# Skaarhoj_BI8-SE-C30.net
KiCad netlist of a schematic drawn in EAGLE
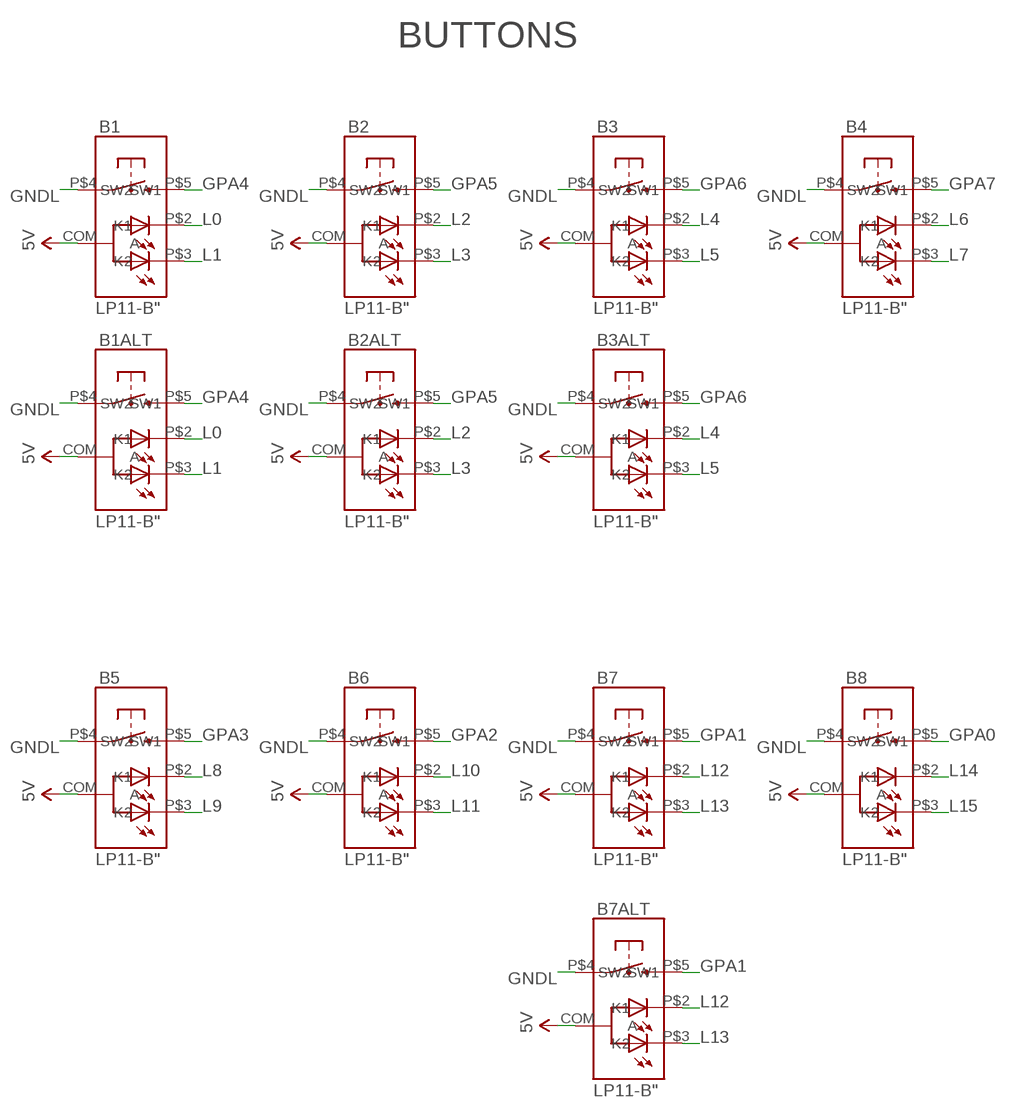
[diagram p0: schematic, sheet 1, part 1 of 2]
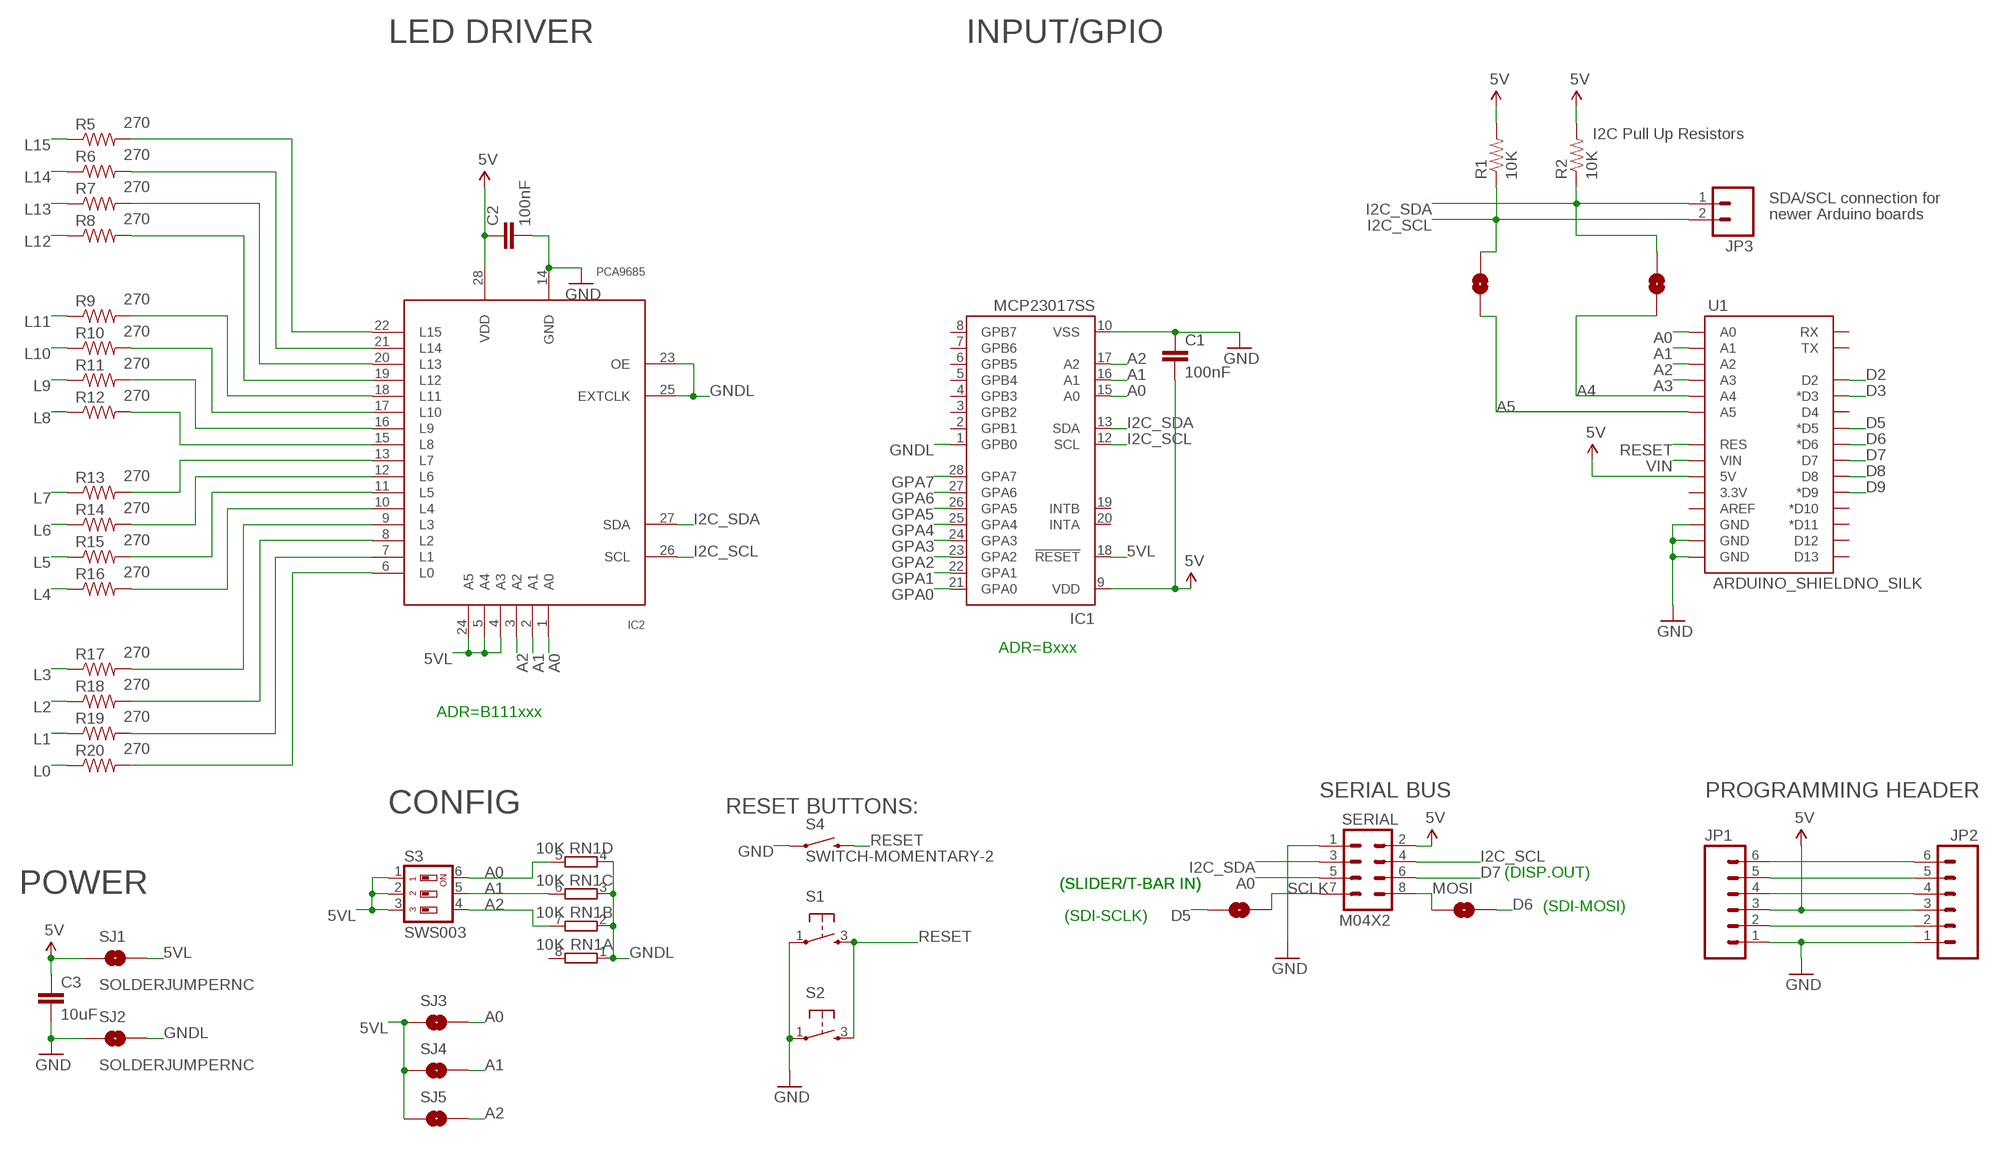
[diagram p1: schematic, sheet 1, part 2 of 2]

(export (version "E")
  (design (tool "Eeschema 10.0.6"))
  (components
    (comp (ref "B1")
      (value "LP11-B\"")
      (footprint "eagle-import:LP11")
      (libsource (lib "eagle-import") (part "LP11-B{dblquote}"))
    )
    (comp (ref "B1ALT")
      (value "LP11-B\"")
      (footprint "eagle-import:LP11")
      (libsource (lib "eagle-import") (part "LP11-B{dblquote}"))
    )
    (comp (ref "B2")
      (value "LP11-B\"")
      (footprint "eagle-import:LP11")
      (libsource (lib "eagle-import") (part "LP11-B{dblquote}"))
    )
    (comp (ref "B2ALT")
      (value "LP11-B\"")
      (footprint "eagle-import:LP11")
      (libsource (lib "eagle-import") (part "LP11-B{dblquote}"))
    )
    (comp (ref "B3")
      (value "LP11-B\"")
      (footprint "eagle-import:LP11")
      (libsource (lib "eagle-import") (part "LP11-B{dblquote}"))
    )
    (comp (ref "B3ALT")
      (value "LP11-B\"")
      (footprint "eagle-import:LP11")
      (libsource (lib "eagle-import") (part "LP11-B{dblquote}"))
    )
    (comp (ref "B4")
      (value "LP11-B\"")
      (footprint "eagle-import:LP11")
      (libsource (lib "eagle-import") (part "LP11-B{dblquote}"))
    )
    (comp (ref "B5")
      (value "LP11-B\"")
      (footprint "eagle-import:LP11")
      (libsource (lib "eagle-import") (part "LP11-B{dblquote}"))
    )
    (comp (ref "B6")
      (value "LP11-B\"")
      (footprint "eagle-import:LP11")
      (libsource (lib "eagle-import") (part "LP11-B{dblquote}"))
    )
    (comp (ref "B7")
      (value "LP11-B\"")
      (footprint "eagle-import:LP11")
      (libsource (lib "eagle-import") (part "LP11-B{dblquote}"))
    )
    (comp (ref "B7ALT")
      (value "LP11-B\"")
      (footprint "eagle-import:LP11")
      (libsource (lib "eagle-import") (part "LP11-B{dblquote}"))
    )
    (comp (ref "B8")
      (value "LP11-B\"")
      (footprint "eagle-import:LP11")
      (libsource (lib "eagle-import") (part "LP11-B{dblquote}"))
    )
    (comp (ref "C1")
      (value "100nF")
      (footprint "eagle-import:0603-CAP")
      (libsource (lib "eagle-import") (part "CAP0603-CAP"))
    )
    (comp (ref "C2")
      (value "100nF")
      (footprint "eagle-import:0603-CAP")
      (libsource (lib "eagle-import") (part "CAP0603-CAP"))
    )
    (comp (ref "C3")
      (value "10uF")
      (footprint "eagle-import:0805")
      (libsource (lib "eagle-import") (part "CAP0805"))
    )
    (comp (ref "IC1")
      (value "MCP23017SS")
      (footprint "eagle-import:SSOP28")
      (fields
        (field (name "MF") "MICROCHIP")
        (field (name "MPN") "MCP23017-E/SS")
        (field (name "MPN_1") "MCP23017-E/SS")
        (field (name "OC_FARNELL") "1467674")
        (field (name "OC_NEWARK") "31K2960")
      )
      (libsource (lib "eagle-import") (part "MCP23017SS"))
    )
    (comp (ref "IC2")
      (value "PCA9685")
      (footprint "eagle-import:TSSOP28")
      (libsource (lib "eagle-import") (part "PCA9685"))
    )
    (comp (ref "JP1")
      (value "M06POLAR")
      (footprint "eagle-import:MOLEX-1X6")
      (libsource (lib "eagle-import") (part "M06POLAR"))
    )
    (comp (ref "JP2")
      (value "M06POLAR")
      (footprint "eagle-import:MOLEX-1X6")
      (libsource (lib "eagle-import") (part "M06POLAR"))
    )
    (comp (ref "JP3")
      (value "M02PTH")
      (footprint "eagle-import:1X02")
      (libsource (lib "eagle-import") (part "M02PTH"))
    )
    (comp (ref "MOSI->D6")
      (value "SOLDERJUMPERNC")
      (footprint "eagle-import:SJ_2S")
      (libsource (lib "eagle-import") (part "SOLDERJUMPERNC"))
    )
    (comp (ref "R1")
      (value "10K")
      (footprint "eagle-import:0603-RES")
      (libsource (lib "eagle-import") (part "RESISTOR0603-RES"))
    )
    (comp (ref "R2")
      (value "10K")
      (footprint "eagle-import:0603-RES")
      (libsource (lib "eagle-import") (part "RESISTOR0603-RES"))
    )
    (comp (ref "R5")
      (value "270")
      (footprint "eagle-import:0603-RES")
      (libsource (lib "eagle-import") (part "RESISTOR0603-RES"))
    )
    (comp (ref "R6")
      (value "270")
      (footprint "eagle-import:0603-RES")
      (libsource (lib "eagle-import") (part "RESISTOR0603-RES"))
    )
    (comp (ref "R7")
      (value "270")
      (footprint "eagle-import:0603-RES")
      (libsource (lib "eagle-import") (part "RESISTOR0603-RES"))
    )
    (comp (ref "R8")
      (value "270")
      (footprint "eagle-import:0603-RES")
      (libsource (lib "eagle-import") (part "RESISTOR0603-RES"))
    )
    (comp (ref "R9")
      (value "270")
      (footprint "eagle-import:0603-RES")
      (libsource (lib "eagle-import") (part "RESISTOR0603-RES"))
    )
    (comp (ref "R10")
      (value "270")
      (footprint "eagle-import:0603-RES")
      (libsource (lib "eagle-import") (part "RESISTOR0603-RES"))
    )
    (comp (ref "R11")
      (value "270")
      (footprint "eagle-import:0603-RES")
      (libsource (lib "eagle-import") (part "RESISTOR0603-RES"))
    )
    (comp (ref "R12")
      (value "270")
      (footprint "eagle-import:0603-RES")
      (libsource (lib "eagle-import") (part "RESISTOR0603-RES"))
    )
    (comp (ref "R13")
      (value "270")
      (footprint "eagle-import:0603-RES")
      (libsource (lib "eagle-import") (part "RESISTOR0603-RES"))
    )
    (comp (ref "R14")
      (value "270")
      (footprint "eagle-import:0603-RES")
      (libsource (lib "eagle-import") (part "RESISTOR0603-RES"))
    )
    (comp (ref "R15")
      (value "270")
      (footprint "eagle-import:0603-RES")
      (libsource (lib "eagle-import") (part "RESISTOR0603-RES"))
    )
    (comp (ref "R16")
      (value "270")
      (footprint "eagle-import:0603-RES")
      (libsource (lib "eagle-import") (part "RESISTOR0603-RES"))
    )
    (comp (ref "R17")
      (value "270")
      (footprint "eagle-import:0603-RES")
      (libsource (lib "eagle-import") (part "RESISTOR0603-RES"))
    )
    (comp (ref "R18")
      (value "270")
      (footprint "eagle-import:0603-RES")
      (libsource (lib "eagle-import") (part "RESISTOR0603-RES"))
    )
    (comp (ref "R19")
      (value "270")
      (footprint "eagle-import:0603-RES")
      (libsource (lib "eagle-import") (part "RESISTOR0603-RES"))
    )
    (comp (ref "R20")
      (value "270")
      (footprint "eagle-import:0603-RES")
      (libsource (lib "eagle-import") (part "RESISTOR0603-RES"))
    )
    (comp (ref "RN1")
      (value "10K")
      (footprint "eagle-import:CAY16_HAND")
      (libsource (lib "eagle-import") (part "4R-NCAY16"))
    )
    (comp (ref "S1")
      (value "TAC_SWITCH")
      (footprint "eagle-import:PUSHBUTTON")
      (libsource (lib "eagle-import") (part "TAC_SWITCH"))
    )
    (comp (ref "S2")
      (value "TAC_SWITCH")
      (footprint "eagle-import:PUSHBUTTON")
      (libsource (lib "eagle-import") (part "TAC_SWITCH"))
    )
    (comp (ref "S3")
      (value "SWS003")
      (footprint "eagle-import:SMS-003")
      (libsource (lib "eagle-import") (part "SWS003"))
    )
    (comp (ref "S3->A2")
      (value "SOLDERJUMPERNC")
      (footprint "eagle-import:SJ_2S")
      (libsource (lib "eagle-import") (part "SOLDERJUMPERNC"))
    )
    (comp (ref "S3->A3")
      (value "SOLDERJUMPERNC")
      (footprint "eagle-import:SJ_2S")
      (libsource (lib "eagle-import") (part "SOLDERJUMPERNC"))
    )
    (comp (ref "S4")
      (value "SWITCH-MOMENTARY-2")
      (footprint "eagle-import:TACTILE_SWITCH_TALL")
      (libsource (lib "eagle-import") (part "SWITCH-MOMENTARY-2"))
    )
    (comp (ref "SCLK->D5")
      (value "SOLDERJUMPERNC")
      (footprint "eagle-import:SJ_2S")
      (libsource (lib "eagle-import") (part "SOLDERJUMPERNC"))
    )
    (comp (ref "SERIAL")
      (value "M04X2")
      (footprint "eagle-import:2X4")
      (libsource (lib "eagle-import") (part "M04X2"))
    )
    (comp (ref "SJ1")
      (value "SOLDERJUMPERNC")
      (footprint "eagle-import:SJ_2S")
      (libsource (lib "eagle-import") (part "SOLDERJUMPERNC"))
    )
    (comp (ref "SJ2")
      (value "SOLDERJUMPERNC")
      (footprint "eagle-import:SJ_2S")
      (libsource (lib "eagle-import") (part "SOLDERJUMPERNC"))
    )
    (comp (ref "SJ3")
      (value "SOLDERJUMPERNC")
      (footprint "eagle-import:SJ_2S")
      (libsource (lib "eagle-import") (part "SOLDERJUMPERNC"))
    )
    (comp (ref "SJ4")
      (value "SOLDERJUMPERNC")
      (footprint "eagle-import:SJ_2S")
      (libsource (lib "eagle-import") (part "SOLDERJUMPERNC"))
    )
    (comp (ref "SJ5")
      (value "SOLDERJUMPERNC")
      (footprint "eagle-import:SJ_2S")
      (libsource (lib "eagle-import") (part "SOLDERJUMPERNC"))
    )
    (comp (ref "U1")
      (value "ARDUINO_SHIELDNO_SILK")
      (footprint "eagle-import:DUEMILANOVE_VIAS")
      (libsource (lib "eagle-import") (part "ARDUINO_SHIELDNO_SILK"))
    )
  )
  (nets
    (net (code "1") (name "/5VL") (class "Default")
      (node (ref "IC1") (pin "18") (pinfunction "~{RESET}_18") (pintype "input"))
      (node (ref "IC2") (pin "24") (pinfunction "A5_24") (pintype "input"))
      (node (ref "IC2") (pin "4") (pinfunction "A3_4") (pintype "input"))
      (node (ref "IC2") (pin "5") (pinfunction "A4_5") (pintype "input"))
      (node (ref "S3") (pin "1") (pinfunction "1_1") (pintype "passive"))
      (node (ref "S3") (pin "2") (pinfunction "2_2") (pintype "passive"))
      (node (ref "S3") (pin "3") (pinfunction "3_3") (pintype "passive"))
      (node (ref "SJ1") (pin "2") (pinfunction "2_2") (pintype "passive"))
      (node (ref "SJ3") (pin "1") (pinfunction "1_1") (pintype "passive"))
      (node (ref "SJ4") (pin "1") (pinfunction "1_1") (pintype "passive"))
      (node (ref "SJ5") (pin "1") (pinfunction "1_1") (pintype "passive"))
    )
    (net (code "2") (name "/A0") (class "Default")
      (node (ref "IC1") (pin "15") (pinfunction "A0_15") (pintype "input"))
      (node (ref "IC2") (pin "1") (pinfunction "A0_1") (pintype "input"))
      (node (ref "RN1") (pin "5") (pinfunction "2_5") (pintype "passive"))
      (node (ref "S3") (pin "6") (pinfunction "6_6") (pintype "passive"))
      (node (ref "SERIAL") (pin "5") (pinfunction "5_5") (pintype "passive"))
      (node (ref "SJ3") (pin "2") (pinfunction "2_2") (pintype "passive"))
      (node (ref "U1") (pin "A0") (pinfunction "A0_A0") (pintype "bidirectional"))
    )
    (net (code "3") (name "/A1") (class "Default")
      (node (ref "IC1") (pin "16") (pinfunction "A1_16") (pintype "input"))
      (node (ref "IC2") (pin "2") (pinfunction "A1_2") (pintype "input"))
      (node (ref "RN1") (pin "6") (pinfunction "2_6") (pintype "passive"))
      (node (ref "S3") (pin "5") (pinfunction "5_5") (pintype "passive"))
      (node (ref "SJ4") (pin "2") (pinfunction "2_2") (pintype "passive"))
      (node (ref "U1") (pin "A1") (pinfunction "A1_A1") (pintype "bidirectional"))
    )
    (net (code "4") (name "/A2") (class "Default")
      (node (ref "IC1") (pin "17") (pinfunction "A2_17") (pintype "input"))
      (node (ref "IC2") (pin "3") (pinfunction "A2_3") (pintype "input"))
      (node (ref "RN1") (pin "7") (pinfunction "2_7") (pintype "passive"))
      (node (ref "S3") (pin "4") (pinfunction "4_4") (pintype "passive"))
      (node (ref "SJ5") (pin "2") (pinfunction "2_2") (pintype "passive"))
      (node (ref "U1") (pin "A2") (pinfunction "A2_A2") (pintype "bidirectional"))
    )
    (net (code "5") (name "/A3") (class "Default")
      (node (ref "U1") (pin "A3") (pinfunction "A3_A3") (pintype "bidirectional"))
    )
    (net (code "6") (name "/A4") (class "Default")
      (node (ref "S3->A3") (pin "2") (pinfunction "2_2") (pintype "passive"))
      (node (ref "U1") (pin "A4") (pinfunction "A4_A4") (pintype "bidirectional"))
    )
    (net (code "7") (name "/A5") (class "Default")
      (node (ref "S3->A2") (pin "2") (pinfunction "2_2") (pintype "passive"))
      (node (ref "U1") (pin "A5") (pinfunction "A5_A5") (pintype "bidirectional"))
    )
    (net (code "8") (name "/D2") (class "Default")
      (node (ref "U1") (pin "D2") (pinfunction "D2_D2") (pintype "bidirectional"))
    )
    (net (code "9") (name "/D3") (class "Default")
      (node (ref "U1") (pin "D3") (pinfunction "*D3_D3") (pintype "bidirectional"))
    )
    (net (code "10") (name "/D5") (class "Default")
      (node (ref "SCLK->D5") (pin "1") (pinfunction "1_1") (pintype "passive"))
      (node (ref "U1") (pin "D5") (pinfunction "*D5_D5") (pintype "bidirectional"))
    )
    (net (code "11") (name "/D6") (class "Default")
      (node (ref "MOSI->D6") (pin "2") (pinfunction "2_2") (pintype "passive"))
      (node (ref "U1") (pin "D6") (pinfunction "*D6_D6") (pintype "bidirectional"))
    )
    (net (code "12") (name "/D7") (class "Default")
      (node (ref "SERIAL") (pin "6") (pinfunction "6_6") (pintype "passive"))
      (node (ref "U1") (pin "D7") (pinfunction "D7_D7") (pintype "bidirectional"))
    )
    (net (code "13") (name "/D8") (class "Default")
      (node (ref "U1") (pin "D8") (pinfunction "D8_D8") (pintype "bidirectional"))
    )
    (net (code "14") (name "/D9") (class "Default")
      (node (ref "U1") (pin "D9") (pinfunction "*D9_D9") (pintype "bidirectional"))
    )
    (net (code "15") (name "/GNDL") (class "Default")
      (node (ref "B1") (pin "P$4") (pinfunction "SW1_P$4") (pintype "bidirectional"))
      (node (ref "B1ALT") (pin "P$4") (pinfunction "SW1_P$4") (pintype "bidirectional"))
      (node (ref "B2") (pin "P$4") (pinfunction "SW1_P$4") (pintype "bidirectional"))
      (node (ref "B2ALT") (pin "P$4") (pinfunction "SW1_P$4") (pintype "bidirectional"))
      (node (ref "B3") (pin "P$4") (pinfunction "SW1_P$4") (pintype "bidirectional"))
      (node (ref "B3ALT") (pin "P$4") (pinfunction "SW1_P$4") (pintype "bidirectional"))
      (node (ref "B4") (pin "P$4") (pinfunction "SW1_P$4") (pintype "bidirectional"))
      (node (ref "B5") (pin "P$4") (pinfunction "SW1_P$4") (pintype "bidirectional"))
      (node (ref "B6") (pin "P$4") (pinfunction "SW1_P$4") (pintype "bidirectional"))
      (node (ref "B7") (pin "P$4") (pinfunction "SW1_P$4") (pintype "bidirectional"))
      (node (ref "B7ALT") (pin "P$4") (pinfunction "SW1_P$4") (pintype "bidirectional"))
      (node (ref "B8") (pin "P$4") (pinfunction "SW1_P$4") (pintype "bidirectional"))
      (node (ref "IC1") (pin "1") (pinfunction "GPB0_1") (pintype "bidirectional"))
      (node (ref "IC2") (pin "23") (pinfunction "OE_23") (pintype "input"))
      (node (ref "IC2") (pin "25") (pinfunction "EXTCLK_25") (pintype "input"))
      (node (ref "RN1") (pin "1") (pinfunction "1_1") (pintype "passive"))
      (node (ref "RN1") (pin "2") (pinfunction "1_2") (pintype "passive"))
      (node (ref "RN1") (pin "3") (pinfunction "1_3") (pintype "passive"))
      (node (ref "RN1") (pin "4") (pinfunction "1_4") (pintype "passive"))
      (node (ref "SJ2") (pin "2") (pinfunction "2_2") (pintype "passive"))
    )
    (net (code "16") (name "/GPA0") (class "Default")
      (node (ref "B8") (pin "P$5") (pinfunction "SW2_P$5") (pintype "bidirectional"))
      (node (ref "IC1") (pin "21") (pinfunction "GPA0_21") (pintype "bidirectional"))
    )
    (net (code "17") (name "/GPA1") (class "Default")
      (node (ref "B7") (pin "P$5") (pinfunction "SW2_P$5") (pintype "bidirectional"))
      (node (ref "B7ALT") (pin "P$5") (pinfunction "SW2_P$5") (pintype "bidirectional"))
      (node (ref "IC1") (pin "22") (pinfunction "GPA1_22") (pintype "bidirectional"))
    )
    (net (code "18") (name "/GPA2") (class "Default")
      (node (ref "B6") (pin "P$5") (pinfunction "SW2_P$5") (pintype "bidirectional"))
      (node (ref "IC1") (pin "23") (pinfunction "GPA2_23") (pintype "bidirectional"))
    )
    (net (code "19") (name "/GPA3") (class "Default")
      (node (ref "B5") (pin "P$5") (pinfunction "SW2_P$5") (pintype "bidirectional"))
      (node (ref "IC1") (pin "24") (pinfunction "GPA3_24") (pintype "bidirectional"))
    )
    (net (code "20") (name "/GPA4") (class "Default")
      (node (ref "B1") (pin "P$5") (pinfunction "SW2_P$5") (pintype "bidirectional"))
      (node (ref "B1ALT") (pin "P$5") (pinfunction "SW2_P$5") (pintype "bidirectional"))
      (node (ref "IC1") (pin "25") (pinfunction "GPA4_25") (pintype "bidirectional"))
    )
    (net (code "21") (name "/GPA5") (class "Default")
      (node (ref "B2") (pin "P$5") (pinfunction "SW2_P$5") (pintype "bidirectional"))
      (node (ref "B2ALT") (pin "P$5") (pinfunction "SW2_P$5") (pintype "bidirectional"))
      (node (ref "IC1") (pin "26") (pinfunction "GPA5_26") (pintype "bidirectional"))
    )
    (net (code "22") (name "/GPA6") (class "Default")
      (node (ref "B3") (pin "P$5") (pinfunction "SW2_P$5") (pintype "bidirectional"))
      (node (ref "B3ALT") (pin "P$5") (pinfunction "SW2_P$5") (pintype "bidirectional"))
      (node (ref "IC1") (pin "27") (pinfunction "GPA6_27") (pintype "bidirectional"))
    )
    (net (code "23") (name "/GPA7") (class "Default")
      (node (ref "B4") (pin "P$5") (pinfunction "SW2_P$5") (pintype "bidirectional"))
      (node (ref "IC1") (pin "28") (pinfunction "GPA7_28") (pintype "bidirectional"))
    )
    (net (code "24") (name "/I2C_SCL") (class "Default")
      (node (ref "IC1") (pin "12") (pinfunction "SCL_12") (pintype "input"))
      (node (ref "IC2") (pin "26") (pinfunction "SCL_26") (pintype "input"))
      (node (ref "JP3") (pin "2") (pinfunction "2_2") (pintype "passive"))
      (node (ref "R1") (pin "1") (pinfunction "1_1") (pintype "passive"))
      (node (ref "S3->A2") (pin "1") (pinfunction "1_1") (pintype "passive"))
      (node (ref "SERIAL") (pin "4") (pinfunction "4_4") (pintype "passive"))
    )
    (net (code "25") (name "/I2C_SDA") (class "Default")
      (node (ref "IC1") (pin "13") (pinfunction "SDA_13") (pintype "bidirectional"))
      (node (ref "IC2") (pin "27") (pinfunction "SDA_27") (pintype "input"))
      (node (ref "JP3") (pin "1") (pinfunction "1_1") (pintype "passive"))
      (node (ref "R2") (pin "1") (pinfunction "1_1") (pintype "passive"))
      (node (ref "S3->A3") (pin "1") (pinfunction "1_1") (pintype "passive"))
      (node (ref "SERIAL") (pin "3") (pinfunction "3_3") (pintype "passive"))
    )
    (net (code "26") (name "/L0") (class "Default")
      (node (ref "B1") (pin "P$2") (pinfunction "K1_P$2") (pintype "bidirectional"))
      (node (ref "B1ALT") (pin "P$2") (pinfunction "K1_P$2") (pintype "bidirectional"))
      (node (ref "R20") (pin "1") (pinfunction "1_1") (pintype "passive"))
    )
    (net (code "27") (name "/L1") (class "Default")
      (node (ref "B1") (pin "P$3") (pinfunction "K2_P$3") (pintype "bidirectional"))
      (node (ref "B1ALT") (pin "P$3") (pinfunction "K2_P$3") (pintype "bidirectional"))
      (node (ref "R19") (pin "1") (pinfunction "1_1") (pintype "passive"))
    )
    (net (code "28") (name "/L2") (class "Default")
      (node (ref "B2") (pin "P$2") (pinfunction "K1_P$2") (pintype "bidirectional"))
      (node (ref "B2ALT") (pin "P$2") (pinfunction "K1_P$2") (pintype "bidirectional"))
      (node (ref "R18") (pin "1") (pinfunction "1_1") (pintype "passive"))
    )
    (net (code "29") (name "/L3") (class "Default")
      (node (ref "B2") (pin "P$3") (pinfunction "K2_P$3") (pintype "bidirectional"))
      (node (ref "B2ALT") (pin "P$3") (pinfunction "K2_P$3") (pintype "bidirectional"))
      (node (ref "R17") (pin "1") (pinfunction "1_1") (pintype "passive"))
    )
    (net (code "30") (name "/L4") (class "Default")
      (node (ref "B3") (pin "P$2") (pinfunction "K1_P$2") (pintype "bidirectional"))
      (node (ref "B3ALT") (pin "P$2") (pinfunction "K1_P$2") (pintype "bidirectional"))
      (node (ref "R16") (pin "1") (pinfunction "1_1") (pintype "passive"))
    )
    (net (code "31") (name "/L5") (class "Default")
      (node (ref "B3") (pin "P$3") (pinfunction "K2_P$3") (pintype "bidirectional"))
      (node (ref "B3ALT") (pin "P$3") (pinfunction "K2_P$3") (pintype "bidirectional"))
      (node (ref "R15") (pin "1") (pinfunction "1_1") (pintype "passive"))
    )
    (net (code "32") (name "/L6") (class "Default")
      (node (ref "B4") (pin "P$2") (pinfunction "K1_P$2") (pintype "bidirectional"))
      (node (ref "R14") (pin "1") (pinfunction "1_1") (pintype "passive"))
    )
    (net (code "33") (name "/L7") (class "Default")
      (node (ref "B4") (pin "P$3") (pinfunction "K2_P$3") (pintype "bidirectional"))
      (node (ref "R13") (pin "1") (pinfunction "1_1") (pintype "passive"))
    )
    (net (code "34") (name "/L8") (class "Default")
      (node (ref "B5") (pin "P$2") (pinfunction "K1_P$2") (pintype "bidirectional"))
      (node (ref "R12") (pin "1") (pinfunction "1_1") (pintype "passive"))
    )
    (net (code "35") (name "/L9") (class "Default")
      (node (ref "B5") (pin "P$3") (pinfunction "K2_P$3") (pintype "bidirectional"))
      (node (ref "R11") (pin "1") (pinfunction "1_1") (pintype "passive"))
    )
    (net (code "36") (name "/L10") (class "Default")
      (node (ref "B6") (pin "P$2") (pinfunction "K1_P$2") (pintype "bidirectional"))
      (node (ref "R10") (pin "1") (pinfunction "1_1") (pintype "passive"))
    )
    (net (code "37") (name "/L11") (class "Default")
      (node (ref "B6") (pin "P$3") (pinfunction "K2_P$3") (pintype "bidirectional"))
      (node (ref "R9") (pin "1") (pinfunction "1_1") (pintype "passive"))
    )
    (net (code "38") (name "/L12") (class "Default")
      (node (ref "B7") (pin "P$2") (pinfunction "K1_P$2") (pintype "bidirectional"))
      (node (ref "B7ALT") (pin "P$2") (pinfunction "K1_P$2") (pintype "bidirectional"))
      (node (ref "R8") (pin "1") (pinfunction "1_1") (pintype "passive"))
    )
    (net (code "39") (name "/L13") (class "Default")
      (node (ref "B7") (pin "P$3") (pinfunction "K2_P$3") (pintype "bidirectional"))
      (node (ref "B7ALT") (pin "P$3") (pinfunction "K2_P$3") (pintype "bidirectional"))
      (node (ref "R7") (pin "1") (pinfunction "1_1") (pintype "passive"))
    )
    (net (code "40") (name "/L14") (class "Default")
      (node (ref "B8") (pin "P$2") (pinfunction "K1_P$2") (pintype "bidirectional"))
      (node (ref "R6") (pin "1") (pinfunction "1_1") (pintype "passive"))
    )
    (net (code "41") (name "/L15") (class "Default")
      (node (ref "B8") (pin "P$3") (pinfunction "K2_P$3") (pintype "bidirectional"))
      (node (ref "R5") (pin "1") (pinfunction "1_1") (pintype "passive"))
    )
    (net (code "42") (name "/MOSI") (class "Default")
      (node (ref "MOSI->D6") (pin "1") (pinfunction "1_1") (pintype "passive"))
      (node (ref "SERIAL") (pin "8") (pinfunction "8_8") (pintype "passive"))
    )
    (net (code "43") (name "/RESET") (class "Default")
      (node (ref "S1") (pin "3") (pinfunction "3_3") (pintype "passive"))
      (node (ref "S2") (pin "3") (pinfunction "3_3") (pintype "passive"))
      (node (ref "S4") (pin "B2") (pinfunction "2_B2") (pintype "passive"))
      (node (ref "U1") (pin "RES") (pinfunction "RES_RES") (pintype "bidirectional"))
    )
    (net (code "44") (name "/SCLK") (class "Default")
      (node (ref "SCLK->D5") (pin "2") (pinfunction "2_2") (pintype "passive"))
      (node (ref "SERIAL") (pin "7") (pinfunction "7_7") (pintype "passive"))
    )
    (net (code "45") (name "/VIN") (class "Default")
      (node (ref "U1") (pin "VIN") (pinfunction "VIN_VIN") (pintype "bidirectional"))
    )
    (net (code "46") (name "5V") (class "Default")
      (node (ref "B1") (pin "COM") (pinfunction "A_COM") (pintype "bidirectional"))
      (node (ref "B1ALT") (pin "COM") (pinfunction "A_COM") (pintype "bidirectional"))
      (node (ref "B2") (pin "COM") (pinfunction "A_COM") (pintype "bidirectional"))
      (node (ref "B2ALT") (pin "COM") (pinfunction "A_COM") (pintype "bidirectional"))
      (node (ref "B3") (pin "COM") (pinfunction "A_COM") (pintype "bidirectional"))
      (node (ref "B3ALT") (pin "COM") (pinfunction "A_COM") (pintype "bidirectional"))
      (node (ref "B4") (pin "COM") (pinfunction "A_COM") (pintype "bidirectional"))
      (node (ref "B5") (pin "COM") (pinfunction "A_COM") (pintype "bidirectional"))
      (node (ref "B6") (pin "COM") (pinfunction "A_COM") (pintype "bidirectional"))
      (node (ref "B7") (pin "COM") (pinfunction "A_COM") (pintype "bidirectional"))
      (node (ref "B7ALT") (pin "COM") (pinfunction "A_COM") (pintype "bidirectional"))
      (node (ref "B8") (pin "COM") (pinfunction "A_COM") (pintype "bidirectional"))
      (node (ref "C1") (pin "2") (pinfunction "2_2") (pintype "passive"))
      (node (ref "C2") (pin "1") (pinfunction "1_1") (pintype "passive"))
      (node (ref "C3") (pin "1") (pinfunction "1_1") (pintype "passive"))
      (node (ref "IC1") (pin "9") (pinfunction "VDD_9") (pintype "power_in"))
      (node (ref "IC2") (pin "28") (pinfunction "VDD_28") (pintype "power_in"))
      (node (ref "JP1") (pin "3") (pinfunction "3_3") (pintype "passive"))
      (node (ref "JP2") (pin "3") (pinfunction "3_3") (pintype "passive"))
      (node (ref "R1") (pin "2") (pinfunction "2_2") (pintype "passive"))
      (node (ref "R2") (pin "2") (pinfunction "2_2") (pintype "passive"))
      (node (ref "SERIAL") (pin "2") (pinfunction "2_2") (pintype "passive"))
      (node (ref "SJ1") (pin "1") (pinfunction "1_1") (pintype "passive"))
      (node (ref "U1") (pin "5V") (pinfunction "5V_5V") (pintype "bidirectional"))
    )
    (net (code "47") (name "GND") (class "Default")
      (node (ref "C1") (pin "1") (pinfunction "1_1") (pintype "passive"))
      (node (ref "C2") (pin "2") (pinfunction "2_2") (pintype "passive"))
      (node (ref "C3") (pin "2") (pinfunction "2_2") (pintype "passive"))
      (node (ref "IC1") (pin "10") (pinfunction "VSS_10") (pintype "power_in"))
      (node (ref "IC2") (pin "14") (pinfunction "GND_14") (pintype "power_in"))
      (node (ref "JP1") (pin "1") (pinfunction "1_1") (pintype "passive"))
      (node (ref "JP2") (pin "1") (pinfunction "1_1") (pintype "passive"))
      (node (ref "S1") (pin "1") (pinfunction "1_1") (pintype "passive"))
      (node (ref "S2") (pin "1") (pinfunction "1_1") (pintype "passive"))
      (node (ref "S4") (pin "A2") (pinfunction "1_A2") (pintype "passive"))
      (node (ref "SERIAL") (pin "1") (pinfunction "1_1") (pintype "passive"))
      (node (ref "SJ2") (pin "1") (pinfunction "1_1") (pintype "passive"))
      (node (ref "U1") (pin "GND@0") (pinfunction "GND_GND@0") (pintype "bidirectional"))
      (node (ref "U1") (pin "GND@1") (pinfunction "GND_GND@1") (pintype "bidirectional"))
      (node (ref "U1") (pin "GND@2") (pinfunction "GND_GND@2") (pintype "bidirectional"))
    )
    (net (code "48") (name "Net-(IC2-L0)") (class "Default")
      (node (ref "IC2") (pin "6") (pinfunction "L0_6") (pintype "output"))
      (node (ref "R20") (pin "2") (pinfunction "2_2") (pintype "passive"))
    )
    (net (code "49") (name "Net-(IC2-L1)") (class "Default")
      (node (ref "IC2") (pin "7") (pinfunction "L1_7") (pintype "output"))
      (node (ref "R19") (pin "2") (pinfunction "2_2") (pintype "passive"))
    )
    (net (code "50") (name "Net-(IC2-L2)") (class "Default")
      (node (ref "IC2") (pin "8") (pinfunction "L2_8") (pintype "output"))
      (node (ref "R18") (pin "2") (pinfunction "2_2") (pintype "passive"))
    )
    (net (code "51") (name "Net-(IC2-L3)") (class "Default")
      (node (ref "IC2") (pin "9") (pinfunction "L3_9") (pintype "output"))
      (node (ref "R17") (pin "2") (pinfunction "2_2") (pintype "passive"))
    )
    (net (code "52") (name "Net-(IC2-L4)") (class "Default")
      (node (ref "IC2") (pin "10") (pinfunction "L4_10") (pintype "output"))
      (node (ref "R16") (pin "2") (pinfunction "2_2") (pintype "passive"))
    )
    (net (code "53") (name "Net-(IC2-L5)") (class "Default")
      (node (ref "IC2") (pin "11") (pinfunction "L5_11") (pintype "output"))
      (node (ref "R15") (pin "2") (pinfunction "2_2") (pintype "passive"))
    )
    (net (code "54") (name "Net-(IC2-L6)") (class "Default")
      (node (ref "IC2") (pin "12") (pinfunction "L6_12") (pintype "output"))
      (node (ref "R14") (pin "2") (pinfunction "2_2") (pintype "passive"))
    )
    (net (code "55") (name "Net-(IC2-L7)") (class "Default")
      (node (ref "IC2") (pin "13") (pinfunction "L7_13") (pintype "output"))
      (node (ref "R13") (pin "2") (pinfunction "2_2") (pintype "passive"))
    )
    (net (code "56") (name "Net-(IC2-L8)") (class "Default")
      (node (ref "IC2") (pin "15") (pinfunction "L8_15") (pintype "output"))
      (node (ref "R12") (pin "2") (pinfunction "2_2") (pintype "passive"))
    )
    (net (code "57") (name "Net-(IC2-L9)") (class "Default")
      (node (ref "IC2") (pin "16") (pinfunction "L9_16") (pintype "output"))
      (node (ref "R11") (pin "2") (pinfunction "2_2") (pintype "passive"))
    )
    (net (code "58") (name "Net-(IC2-L10)") (class "Default")
      (node (ref "IC2") (pin "17") (pinfunction "L10_17") (pintype "output"))
      (node (ref "R10") (pin "2") (pinfunction "2_2") (pintype "passive"))
    )
    (net (code "59") (name "Net-(IC2-L11)") (class "Default")
      (node (ref "IC2") (pin "18") (pinfunction "L11_18") (pintype "output"))
      (node (ref "R9") (pin "2") (pinfunction "2_2") (pintype "passive"))
    )
    (net (code "60") (name "Net-(IC2-L12)") (class "Default")
      (node (ref "IC2") (pin "19") (pinfunction "L12_19") (pintype "output"))
      (node (ref "R8") (pin "2") (pinfunction "2_2") (pintype "passive"))
    )
    (net (code "61") (name "Net-(IC2-L13)") (class "Default")
      (node (ref "IC2") (pin "20") (pinfunction "L13_20") (pintype "output"))
      (node (ref "R7") (pin "2") (pinfunction "2_2") (pintype "passive"))
    )
    (net (code "62") (name "Net-(IC2-L14)") (class "Default")
      (node (ref "IC2") (pin "21") (pinfunction "L14_21") (pintype "output"))
      (node (ref "R6") (pin "2") (pinfunction "2_2") (pintype "passive"))
    )
    (net (code "63") (name "Net-(IC2-L15)") (class "Default")
      (node (ref "IC2") (pin "22") (pinfunction "L15_22") (pintype "output"))
      (node (ref "R5") (pin "2") (pinfunction "2_2") (pintype "passive"))
    )
    (net (code "64") (name "Net-(JP1-Pad2)") (class "Default")
      (node (ref "JP1") (pin "2") (pinfunction "2_2") (pintype "passive"))
      (node (ref "JP2") (pin "2") (pinfunction "2_2") (pintype "passive"))
    )
    (net (code "65") (name "Net-(JP1-Pad4)") (class "Default")
      (node (ref "JP1") (pin "4") (pinfunction "4_4") (pintype "passive"))
      (node (ref "JP2") (pin "4") (pinfunction "4_4") (pintype "passive"))
    )
    (net (code "66") (name "Net-(JP1-Pad5)") (class "Default")
      (node (ref "JP1") (pin "5") (pinfunction "5_5") (pintype "passive"))
      (node (ref "JP2") (pin "5") (pinfunction "5_5") (pintype "passive"))
    )
    (net (code "67") (name "Net-(JP1-Pad6)") (class "Default")
      (node (ref "JP1") (pin "6") (pinfunction "6_6") (pintype "passive"))
      (node (ref "JP2") (pin "6") (pinfunction "6_6") (pintype "passive"))
    )
    (net (code "68") (name "unconnected-(IC1-GPB1-Pad2)") (class "Default")
      (node (ref "IC1") (pin "2") (pinfunction "GPB1_2") (pintype "bidirectional"))
    )
    (net (code "69") (name "unconnected-(IC1-GPB2-Pad3)") (class "Default")
      (node (ref "IC1") (pin "3") (pinfunction "GPB2_3") (pintype "bidirectional"))
    )
    (net (code "70") (name "unconnected-(IC1-GPB3-Pad4)") (class "Default")
      (node (ref "IC1") (pin "4") (pinfunction "GPB3_4") (pintype "bidirectional"))
    )
    (net (code "71") (name "unconnected-(IC1-GPB4-Pad5)") (class "Default")
      (node (ref "IC1") (pin "5") (pinfunction "GPB4_5") (pintype "bidirectional"))
    )
    (net (code "72") (name "unconnected-(IC1-GPB5-Pad6)") (class "Default")
      (node (ref "IC1") (pin "6") (pinfunction "GPB5_6") (pintype "bidirectional"))
    )
    (net (code "73") (name "unconnected-(IC1-GPB6-Pad7)") (class "Default")
      (node (ref "IC1") (pin "7") (pinfunction "GPB6_7") (pintype "bidirectional"))
    )
    (net (code "74") (name "unconnected-(IC1-GPB7-Pad8)") (class "Default")
      (node (ref "IC1") (pin "8") (pinfunction "GPB7_8") (pintype "bidirectional"))
    )
    (net (code "75") (name "unconnected-(IC1-INTA-Pad20)") (class "Default")
      (node (ref "IC1") (pin "20") (pinfunction "INTA_20") (pintype "output"))
    )
    (net (code "76") (name "unconnected-(IC1-INTB-Pad19)") (class "Default")
      (node (ref "IC1") (pin "19") (pinfunction "INTB_19") (pintype "output"))
    )
    (net (code "77") (name "unconnected-(RN1A-2-Pad8)") (class "Default")
      (node (ref "RN1") (pin "8") (pinfunction "2_8") (pintype "passive"))
    )
    (net (code "78") (name "unconnected-(U1-*D10-PadD10)") (class "Default")
      (node (ref "U1") (pin "D10") (pinfunction "*D10_D10") (pintype "bidirectional"))
    )
    (net (code "79") (name "unconnected-(U1-*D11-PadD11)") (class "Default")
      (node (ref "U1") (pin "D11") (pinfunction "*D11_D11") (pintype "bidirectional"))
    )
    (net (code "80") (name "unconnected-(U1-Pad3.3V)") (class "Default")
      (node (ref "U1") (pin "3.3V") (pinfunction "3.3V_3.3V") (pintype "bidirectional"))
    )
    (net (code "81") (name "unconnected-(U1-PadAREF)") (class "Default")
      (node (ref "U1") (pin "AREF") (pinfunction "AREF_AREF") (pintype "bidirectional"))
    )
    (net (code "82") (name "unconnected-(U1-PadD4)") (class "Default")
      (node (ref "U1") (pin "D4") (pinfunction "D4_D4") (pintype "bidirectional"))
    )
    (net (code "83") (name "unconnected-(U1-PadD12)") (class "Default")
      (node (ref "U1") (pin "D12") (pinfunction "D12_D12") (pintype "bidirectional"))
    )
    (net (code "84") (name "unconnected-(U1-PadD13)") (class "Default")
      (node (ref "U1") (pin "D13") (pinfunction "D13_D13") (pintype "bidirectional"))
    )
    (net (code "85") (name "unconnected-(U1-PadRX)") (class "Default")
      (node (ref "U1") (pin "RX") (pinfunction "RX_RX") (pintype "bidirectional"))
    )
    (net (code "86") (name "unconnected-(U1-PadTX)") (class "Default")
      (node (ref "U1") (pin "TX") (pinfunction "TX_TX") (pintype "bidirectional"))
    )
  )
)
